# WROOM32.net
KiCad netlist of a schematic drawn in Altium Designer
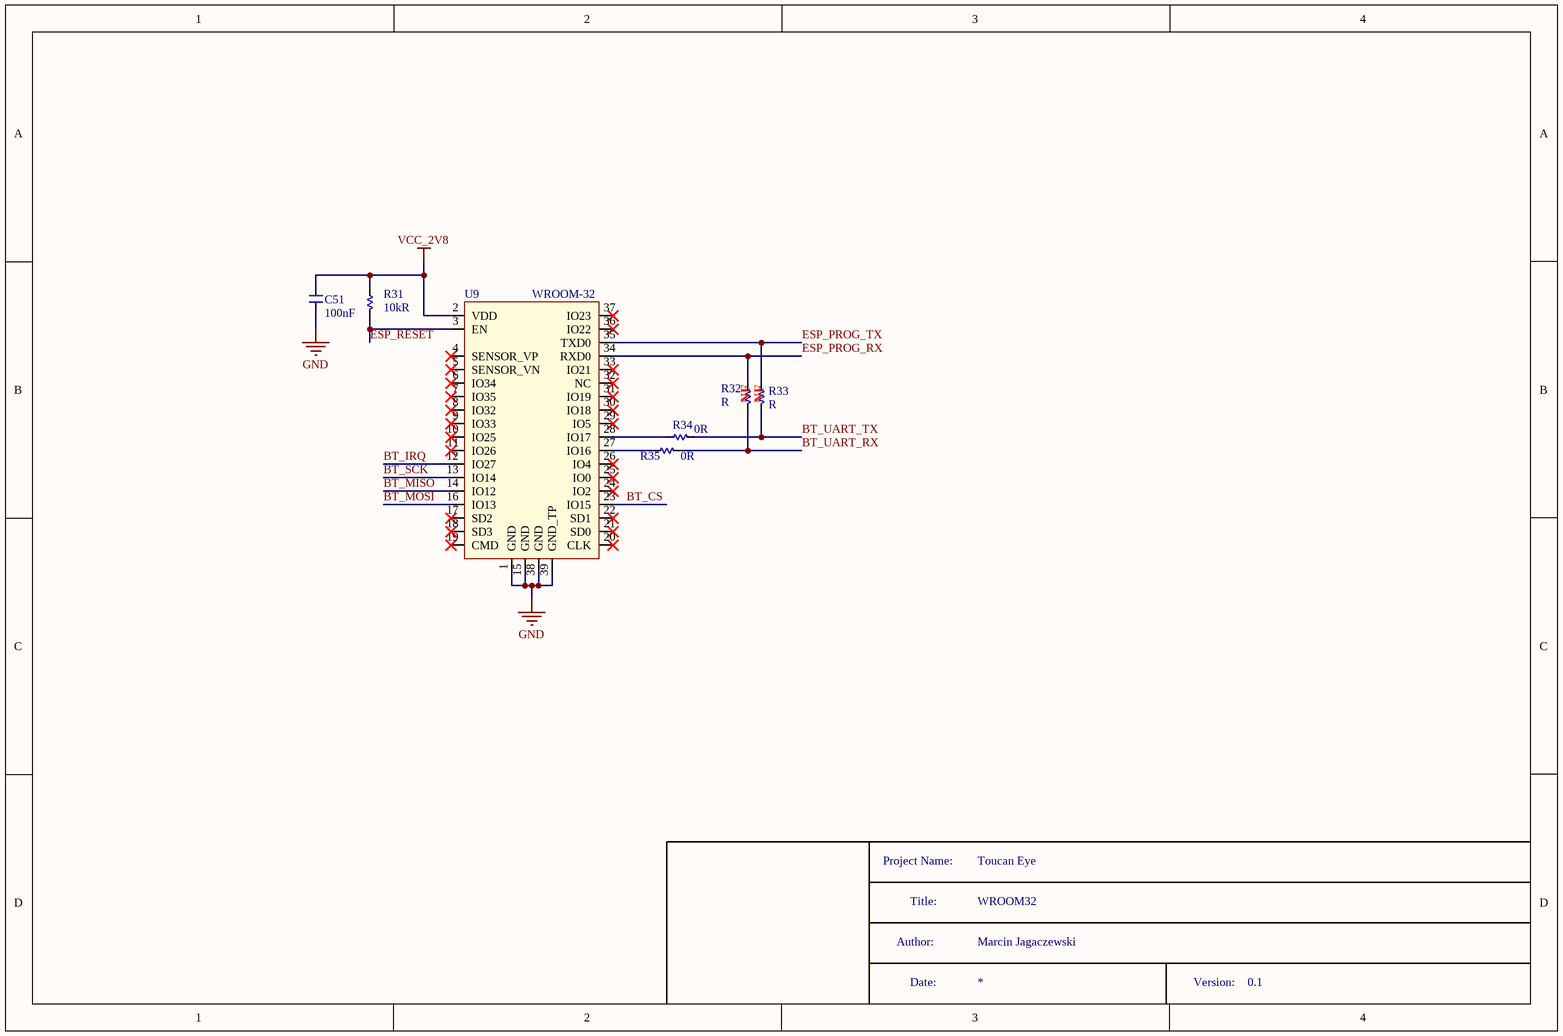
[diagram p0: WROOM32.SchDoc]

(export (version "E")
  (design (tool "Eeschema 10.0.6"))
  (components
    (comp (ref "C51")
      (value "C0201_100n_GRM033R6YA104KE14D")
      (footprint "C_0201")
      (description "Multilayer Ceramic Capacitors MLCC - SMD/SMT 0201 0.10uF 35volts *Derate Voltage/Temp")
      (fields
        (field (name "MANUFACTURER") "Murata")
        (field (name "MANUFACTURER PART NUMBER") "GRM033R6YA104KE14D")
        (field (name "CAPACITANCE") "100nF")
      )
      (libsource (lib "CAP") (part "C0201_100n_GRM033R6YA104KE14D"))
    )
    (comp (ref "R31")
      (value "R0201_10k_ERJ-1GNF1002C")
      (footprint "R_0201")
      (description "RESISTOR, 0201, 0.05W, 1%, 10K")
      (fields
        (field (name "MANUFACTURER") "Panasonic ECG")
        (field (name "MANUFACTURER PART NUMBER") "ERJ-1GNF1002C")
        (field (name "RESISTANCE") "10kR")
      )
      (libsource (lib "RES") (part "R0201_10k_ERJ-1GNF1002C"))
    )
    (comp (ref "R32")
      (value "R")
      (footprint "R_0201_NF")
      (fields (field (name "Comment") "(NDI)0201"))
      (libsource (lib "RES") (part "(NDI)0201"))
    )
    (comp (ref "R33")
      (value "R")
      (footprint "R_0201_NF")
      (fields (field (name "Comment") "(NDI)0201"))
      (libsource (lib "RES") (part "(NDI)0201"))
    )
    (comp (ref "R34")
      (value "R0201_0_ERJ-1GN0R00C")
      (footprint "R_0201")
      (description "RES SMD 0.0OHM JUMPER 1/20W 0201")
      (fields
        (field (name "MANUFACTURER") "Panasonic")
        (field (name "MANUFACTURER PART NUMBER") "ERJ-1GN0R00C")
        (field (name "RESISTANCE") "0R")
      )
      (libsource (lib "RES") (part "R0201_0_ERJ-1GN0R00C"))
    )
    (comp (ref "R35")
      (value "R0201_0_ERJ-1GN0R00C")
      (footprint "R_0201")
      (description "RES SMD 0.0OHM JUMPER 1/20W 0201")
      (fields
        (field (name "MANUFACTURER") "Panasonic")
        (field (name "MANUFACTURER PART NUMBER") "ERJ-1GN0R00C")
        (field (name "RESISTANCE") "0R")
      )
      (libsource (lib "RES") (part "R0201_0_ERJ-1GN0R00C"))
    )
    (comp (ref "U9") (value "WROOM-32") (footprint "WROOM-32") (libsource (lib "CHIP") (part "WROOM-32")))
  )
  (nets
    (net (code "1") (name "/BT_CS") (class "Default")
      (node (ref "U9") (pin "23") (pinfunction "IO15_23") (pintype "passive"))
    )
    (net (code "2") (name "/BT_IRQ") (class "Default")
      (node (ref "U9") (pin "12") (pinfunction "IO27_12") (pintype "passive"))
    )
    (net (code "3") (name "/BT_MISO") (class "Default")
      (node (ref "U9") (pin "14") (pinfunction "IO12_14") (pintype "passive"))
    )
    (net (code "4") (name "/BT_MOSI") (class "Default")
      (node (ref "U9") (pin "16") (pinfunction "IO13_16") (pintype "passive"))
    )
    (net (code "5") (name "/BT_SCK") (class "Default")
      (node (ref "U9") (pin "13") (pinfunction "IO14_13") (pintype "passive"))
    )
    (net (code "6") (name "/BT_UART_RX") (class "Default")
      (node (ref "R32") (pin "1") (pinfunction "1_1") (pintype "power_in"))
      (node (ref "R35") (pin "1") (pinfunction "1_1") (pintype "power_in"))
    )
    (net (code "7") (name "/BT_UART_TX") (class "Default")
      (node (ref "R33") (pin "1") (pinfunction "1_1") (pintype "power_in"))
      (node (ref "R34") (pin "1") (pinfunction "1_1") (pintype "power_in"))
    )
    (net (code "8") (name "/ESP_PROG_RX") (class "Default")
      (node (ref "R32") (pin "2") (pinfunction "2_2") (pintype "power_in"))
      (node (ref "U9") (pin "34") (pinfunction "RXD0_34") (pintype "passive"))
    )
    (net (code "9") (name "/ESP_PROG_TX") (class "Default")
      (node (ref "R33") (pin "2") (pinfunction "2_2") (pintype "power_in"))
      (node (ref "U9") (pin "35") (pinfunction "TXD0_35") (pintype "passive"))
    )
    (net (code "10") (name "/ESP_RESET") (class "Default")
      (node (ref "R31") (pin "1") (pinfunction "1_1") (pintype "power_in"))
      (node (ref "U9") (pin "3") (pinfunction "EN_3") (pintype "passive"))
    )
    (net (code "11") (name "GND") (class "Default")
      (node (ref "C51") (pin "1") (pinfunction "1_1") (pintype "passive"))
      (node (ref "U9") (pin "1") (pinfunction "GND_1") (pintype "passive"))
      (node (ref "U9") (pin "15") (pinfunction "GND_15") (pintype "passive"))
      (node (ref "U9") (pin "38") (pinfunction "GND_38") (pintype "power_in"))
      (node (ref "U9") (pin "39") (pinfunction "GND_TP_39") (pintype "passive"))
    )
    (net (code "12") (name "Net-(U9-IO16)") (class "Default")
      (node (ref "R35") (pin "2") (pinfunction "2_2") (pintype "power_in"))
      (node (ref "U9") (pin "27") (pinfunction "IO16_27") (pintype "passive"))
    )
    (net (code "13") (name "Net-(U9-IO17)") (class "Default")
      (node (ref "R34") (pin "2") (pinfunction "2_2") (pintype "power_in"))
      (node (ref "U9") (pin "28") (pinfunction "IO17_28") (pintype "passive"))
    )
    (net (code "14") (name "VCC_2V8") (class "Default")
      (node (ref "C51") (pin "2") (pinfunction "2_2") (pintype "passive"))
      (node (ref "R31") (pin "2") (pinfunction "2_2") (pintype "power_in"))
      (node (ref "U9") (pin "2") (pinfunction "VDD_2") (pintype "passive"))
    )
    (net (code "15") (name "unconnected-(U9-CLK-Pad20)") (class "Default")
      (node (ref "U9") (pin "20") (pinfunction "CLK_20") (pintype "passive+no_connect"))
    )
    (net (code "16") (name "unconnected-(U9-CMD-Pad19)") (class "Default")
      (node (ref "U9") (pin "19") (pinfunction "CMD_19") (pintype "passive+no_connect"))
    )
    (net (code "17") (name "unconnected-(U9-IO0-Pad25)") (class "Default")
      (node (ref "U9") (pin "25") (pinfunction "IO0_25") (pintype "passive+no_connect"))
    )
    (net (code "18") (name "unconnected-(U9-IO2-Pad24)") (class "Default")
      (node (ref "U9") (pin "24") (pinfunction "IO2_24") (pintype "passive+no_connect"))
    )
    (net (code "19") (name "unconnected-(U9-IO4-Pad26)") (class "Default")
      (node (ref "U9") (pin "26") (pinfunction "IO4_26") (pintype "passive+no_connect"))
    )
    (net (code "20") (name "unconnected-(U9-IO5-Pad29)") (class "Default")
      (node (ref "U9") (pin "29") (pinfunction "IO5_29") (pintype "passive+no_connect"))
    )
    (net (code "21") (name "unconnected-(U9-IO18-Pad30)") (class "Default")
      (node (ref "U9") (pin "30") (pinfunction "IO18_30") (pintype "passive+no_connect"))
    )
    (net (code "22") (name "unconnected-(U9-IO19-Pad31)") (class "Default")
      (node (ref "U9") (pin "31") (pinfunction "IO19_31") (pintype "passive+no_connect"))
    )
    (net (code "23") (name "unconnected-(U9-IO21-Pad33)") (class "Default")
      (node (ref "U9") (pin "33") (pinfunction "IO21_33") (pintype "passive+no_connect"))
    )
    (net (code "24") (name "unconnected-(U9-IO22-Pad36)") (class "Default")
      (node (ref "U9") (pin "36") (pinfunction "IO22_36") (pintype "passive+no_connect"))
    )
    (net (code "25") (name "unconnected-(U9-IO23-Pad37)") (class "Default")
      (node (ref "U9") (pin "37") (pinfunction "IO23_37") (pintype "passive+no_connect"))
    )
    (net (code "26") (name "unconnected-(U9-IO25-Pad10)") (class "Default")
      (node (ref "U9") (pin "10") (pinfunction "IO25_10") (pintype "passive+no_connect"))
    )
    (net (code "27") (name "unconnected-(U9-IO26-Pad11)") (class "Default")
      (node (ref "U9") (pin "11") (pinfunction "IO26_11") (pintype "passive+no_connect"))
    )
    (net (code "28") (name "unconnected-(U9-IO32-Pad8)") (class "Default")
      (node (ref "U9") (pin "8") (pinfunction "IO32_8") (pintype "passive+no_connect"))
    )
    (net (code "29") (name "unconnected-(U9-IO33-Pad9)") (class "Default")
      (node (ref "U9") (pin "9") (pinfunction "IO33_9") (pintype "passive+no_connect"))
    )
    (net (code "30") (name "unconnected-(U9-IO34-Pad6)") (class "Default")
      (node (ref "U9") (pin "6") (pinfunction "IO34_6") (pintype "passive+no_connect"))
    )
    (net (code "31") (name "unconnected-(U9-IO35-Pad7)") (class "Default")
      (node (ref "U9") (pin "7") (pinfunction "IO35_7") (pintype "passive+no_connect"))
    )
    (net (code "32") (name "unconnected-(U9-NC-Pad32)") (class "Default")
      (node (ref "U9") (pin "32") (pinfunction "NC_32") (pintype "passive+no_connect"))
    )
    (net (code "33") (name "unconnected-(U9-SD0-Pad21)") (class "Default")
      (node (ref "U9") (pin "21") (pinfunction "SD0_21") (pintype "passive+no_connect"))
    )
    (net (code "34") (name "unconnected-(U9-SD1-Pad22)") (class "Default")
      (node (ref "U9") (pin "22") (pinfunction "SD1_22") (pintype "passive+no_connect"))
    )
    (net (code "35") (name "unconnected-(U9-SD2-Pad17)") (class "Default")
      (node (ref "U9") (pin "17") (pinfunction "SD2_17") (pintype "passive+no_connect"))
    )
    (net (code "36") (name "unconnected-(U9-SD3-Pad18)") (class "Default")
      (node (ref "U9") (pin "18") (pinfunction "SD3_18") (pintype "passive+no_connect"))
    )
    (net (code "37") (name "unconnected-(U9-SENSOR_VN-Pad5)") (class "Default")
      (node (ref "U9") (pin "5") (pinfunction "SENSOR_VN_5") (pintype "passive+no_connect"))
    )
    (net (code "38") (name "unconnected-(U9-SENSOR_VP-Pad4)") (class "Default")
      (node (ref "U9") (pin "4") (pinfunction "SENSOR_VP_4") (pintype "passive+no_connect"))
    )
  )
)
